# apa102-breakout.net
KiCad netlist of a schematic drawn in EAGLE
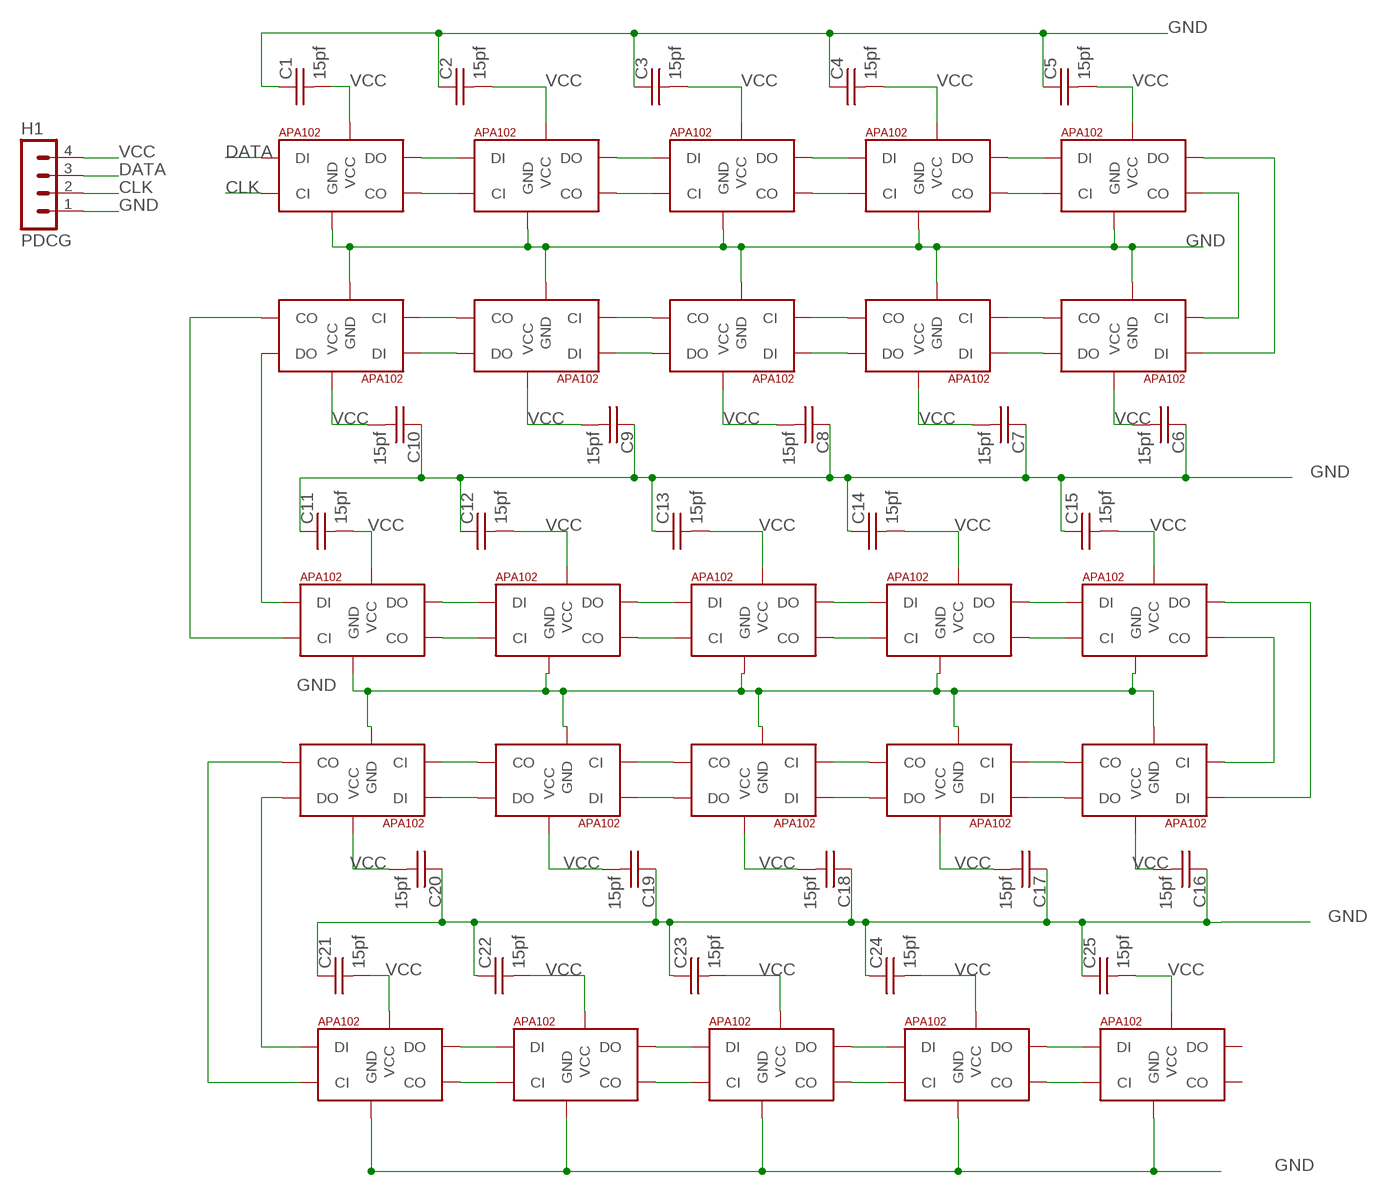
[diagram p0: schematic, sheet 1]
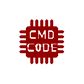
[diagram p1: schematic, sheet 2]

(export (version "E")
  (design (tool "Eeschema 10.0.6"))
  (components
    (comp (ref "C1")
      (value "15pf")
      (footprint "eagle-import:C0805")
      (libsource (lib "eagle-import") (part "C-USC0805"))
    )
    (comp (ref "C2")
      (value "15pf")
      (footprint "eagle-import:C0805")
      (libsource (lib "eagle-import") (part "C-USC0805"))
    )
    (comp (ref "C3")
      (value "15pf")
      (footprint "eagle-import:C0805")
      (libsource (lib "eagle-import") (part "C-USC0805"))
    )
    (comp (ref "C4")
      (value "15pf")
      (footprint "eagle-import:C0805")
      (libsource (lib "eagle-import") (part "C-USC0805"))
    )
    (comp (ref "C5")
      (value "15pf")
      (footprint "eagle-import:C0805")
      (libsource (lib "eagle-import") (part "C-USC0805"))
    )
    (comp (ref "C6")
      (value "15pf")
      (footprint "eagle-import:C0805")
      (libsource (lib "eagle-import") (part "C-USC0805"))
    )
    (comp (ref "C7")
      (value "15pf")
      (footprint "eagle-import:C0805")
      (libsource (lib "eagle-import") (part "C-USC0805"))
    )
    (comp (ref "C8")
      (value "15pf")
      (footprint "eagle-import:C0805")
      (libsource (lib "eagle-import") (part "C-USC0805"))
    )
    (comp (ref "C9")
      (value "15pf")
      (footprint "eagle-import:C0805")
      (libsource (lib "eagle-import") (part "C-USC0805"))
    )
    (comp (ref "C10")
      (value "15pf")
      (footprint "eagle-import:C0805")
      (libsource (lib "eagle-import") (part "C-USC0805"))
    )
    (comp (ref "C11")
      (value "15pf")
      (footprint "eagle-import:C0805")
      (libsource (lib "eagle-import") (part "C-USC0805"))
    )
    (comp (ref "C12")
      (value "15pf")
      (footprint "eagle-import:C0805")
      (libsource (lib "eagle-import") (part "C-USC0805"))
    )
    (comp (ref "C13")
      (value "15pf")
      (footprint "eagle-import:C0805")
      (libsource (lib "eagle-import") (part "C-USC0805"))
    )
    (comp (ref "C14")
      (value "15pf")
      (footprint "eagle-import:C0805")
      (libsource (lib "eagle-import") (part "C-USC0805"))
    )
    (comp (ref "C15")
      (value "15pf")
      (footprint "eagle-import:C0805")
      (libsource (lib "eagle-import") (part "C-USC0805"))
    )
    (comp (ref "C16")
      (value "15pf")
      (footprint "eagle-import:C0805")
      (libsource (lib "eagle-import") (part "C-USC0805"))
    )
    (comp (ref "C17")
      (value "15pf")
      (footprint "eagle-import:C0805")
      (libsource (lib "eagle-import") (part "C-USC0805"))
    )
    (comp (ref "C18")
      (value "15pf")
      (footprint "eagle-import:C0805")
      (libsource (lib "eagle-import") (part "C-USC0805"))
    )
    (comp (ref "C19")
      (value "15pf")
      (footprint "eagle-import:C0805")
      (libsource (lib "eagle-import") (part "C-USC0805"))
    )
    (comp (ref "C20")
      (value "15pf")
      (footprint "eagle-import:C0805")
      (libsource (lib "eagle-import") (part "C-USC0805"))
    )
    (comp (ref "C21")
      (value "15pf")
      (footprint "eagle-import:C0805")
      (libsource (lib "eagle-import") (part "C-USC0805"))
    )
    (comp (ref "C22")
      (value "15pf")
      (footprint "eagle-import:C0805")
      (libsource (lib "eagle-import") (part "C-USC0805"))
    )
    (comp (ref "C23")
      (value "15pf")
      (footprint "eagle-import:C0805")
      (libsource (lib "eagle-import") (part "C-USC0805"))
    )
    (comp (ref "C24")
      (value "15pf")
      (footprint "eagle-import:C0805")
      (libsource (lib "eagle-import") (part "C-USC0805"))
    )
    (comp (ref "C25")
      (value "15pf")
      (footprint "eagle-import:C0805")
      (libsource (lib "eagle-import") (part "C-USC0805"))
    )
    (comp (ref "H1")
      (value "PDCG")
      (footprint "eagle-import:MA04-1")
      (libsource (lib "eagle-import") (part "MA04-1"))
    )
    (comp (ref "U$2")
      (value "APA1025050")
      (footprint "eagle-import:APA102_5050")
      (libsource (lib "eagle-import") (part "APA1025050"))
    )
    (comp (ref "U$3")
      (value "APA1025050")
      (footprint "eagle-import:APA102_5050")
      (libsource (lib "eagle-import") (part "APA1025050"))
    )
    (comp (ref "U$4")
      (value "APA1025050")
      (footprint "eagle-import:APA102_5050")
      (libsource (lib "eagle-import") (part "APA1025050"))
    )
    (comp (ref "U$5")
      (value "APA1025050")
      (footprint "eagle-import:APA102_5050")
      (libsource (lib "eagle-import") (part "APA1025050"))
    )
    (comp (ref "U$6")
      (value "APA1025050")
      (footprint "eagle-import:APA102_5050")
      (libsource (lib "eagle-import") (part "APA1025050"))
    )
    (comp (ref "U$7")
      (value "APA1025050")
      (footprint "eagle-import:APA102_5050")
      (libsource (lib "eagle-import") (part "APA1025050"))
    )
    (comp (ref "U$8")
      (value "APA1025050")
      (footprint "eagle-import:APA102_5050")
      (libsource (lib "eagle-import") (part "APA1025050"))
    )
    (comp (ref "U$9")
      (value "APA1025050")
      (footprint "eagle-import:APA102_5050")
      (libsource (lib "eagle-import") (part "APA1025050"))
    )
    (comp (ref "U$10")
      (value "APA1025050")
      (footprint "eagle-import:APA102_5050")
      (libsource (lib "eagle-import") (part "APA1025050"))
    )
    (comp (ref "U$11")
      (value "APA1025050")
      (footprint "eagle-import:APA102_5050")
      (libsource (lib "eagle-import") (part "APA1025050"))
    )
    (comp (ref "U$12")
      (value "APA1025050")
      (footprint "eagle-import:APA102_5050")
      (libsource (lib "eagle-import") (part "APA1025050"))
    )
    (comp (ref "U$13")
      (value "APA1025050")
      (footprint "eagle-import:APA102_5050")
      (libsource (lib "eagle-import") (part "APA1025050"))
    )
    (comp (ref "U$14")
      (value "APA1025050")
      (footprint "eagle-import:APA102_5050")
      (libsource (lib "eagle-import") (part "APA1025050"))
    )
    (comp (ref "U$15")
      (value "APA1025050")
      (footprint "eagle-import:APA102_5050")
      (libsource (lib "eagle-import") (part "APA1025050"))
    )
    (comp (ref "U$16")
      (value "APA1025050")
      (footprint "eagle-import:APA102_5050")
      (libsource (lib "eagle-import") (part "APA1025050"))
    )
    (comp (ref "U$17")
      (value "APA1025050")
      (footprint "eagle-import:APA102_5050")
      (libsource (lib "eagle-import") (part "APA1025050"))
    )
    (comp (ref "U$18")
      (value "APA1025050")
      (footprint "eagle-import:APA102_5050")
      (libsource (lib "eagle-import") (part "APA1025050"))
    )
    (comp (ref "U$19")
      (value "APA1025050")
      (footprint "eagle-import:APA102_5050")
      (libsource (lib "eagle-import") (part "APA1025050"))
    )
    (comp (ref "U$20")
      (value "APA1025050")
      (footprint "eagle-import:APA102_5050")
      (libsource (lib "eagle-import") (part "APA1025050"))
    )
    (comp (ref "U$21")
      (value "APA1025050")
      (footprint "eagle-import:APA102_5050")
      (libsource (lib "eagle-import") (part "APA1025050"))
    )
    (comp (ref "U$22")
      (value "APA1025050")
      (footprint "eagle-import:APA102_5050")
      (libsource (lib "eagle-import") (part "APA1025050"))
    )
    (comp (ref "U$23")
      (value "APA1025050")
      (footprint "eagle-import:APA102_5050")
      (libsource (lib "eagle-import") (part "APA1025050"))
    )
    (comp (ref "U$24")
      (value "APA1025050")
      (footprint "eagle-import:APA102_5050")
      (libsource (lib "eagle-import") (part "APA1025050"))
    )
    (comp (ref "U$25")
      (value "APA1025050")
      (footprint "eagle-import:APA102_5050")
      (libsource (lib "eagle-import") (part "APA1025050"))
    )
    (comp (ref "U$26")
      (value "APA1025050")
      (footprint "eagle-import:APA102_5050")
      (libsource (lib "eagle-import") (part "APA1025050"))
    )
    (comp (ref "U$1")
      (value "CMD_C0DE_LOGOCMD_C0DE_LOGO_TOP")
      (footprint "eagle-import:CMD_C0DE_LOGO_TOP")
      (libsource (lib "eagle-import") (part "CMD_C0DE_LOGOCMD_C0DE_LOGO_TOP"))
    )
  )
  (nets
    (net (code "1") (name "CLK") (class "Default")
      (node (ref "H1") (pin "2") (pinfunction "2_2") (pintype "passive"))
      (node (ref "U$2") (pin "5") (pinfunction "CI_5") (pintype "bidirectional"))
    )
    (net (code "2") (name "DATA") (class "Default")
      (node (ref "H1") (pin "3") (pinfunction "3_3") (pintype "passive"))
      (node (ref "U$2") (pin "4") (pinfunction "DI_4") (pintype "bidirectional"))
    )
    (net (code "3") (name "GND") (class "Default")
      (node (ref "C1") (pin "1") (pinfunction "1_1") (pintype "passive"))
      (node (ref "C10") (pin "1") (pinfunction "1_1") (pintype "passive"))
      (node (ref "C11") (pin "1") (pinfunction "1_1") (pintype "passive"))
      (node (ref "C12") (pin "1") (pinfunction "1_1") (pintype "passive"))
      (node (ref "C13") (pin "1") (pinfunction "1_1") (pintype "passive"))
      (node (ref "C14") (pin "1") (pinfunction "1_1") (pintype "passive"))
      (node (ref "C15") (pin "1") (pinfunction "1_1") (pintype "passive"))
      (node (ref "C16") (pin "1") (pinfunction "1_1") (pintype "passive"))
      (node (ref "C17") (pin "1") (pinfunction "1_1") (pintype "passive"))
      (node (ref "C18") (pin "1") (pinfunction "1_1") (pintype "passive"))
      (node (ref "C19") (pin "1") (pinfunction "1_1") (pintype "passive"))
      (node (ref "C2") (pin "1") (pinfunction "1_1") (pintype "passive"))
      (node (ref "C20") (pin "1") (pinfunction "1_1") (pintype "passive"))
      (node (ref "C21") (pin "1") (pinfunction "1_1") (pintype "passive"))
      (node (ref "C22") (pin "1") (pinfunction "1_1") (pintype "passive"))
      (node (ref "C23") (pin "1") (pinfunction "1_1") (pintype "passive"))
      (node (ref "C24") (pin "1") (pinfunction "1_1") (pintype "passive"))
      (node (ref "C25") (pin "1") (pinfunction "1_1") (pintype "passive"))
      (node (ref "C3") (pin "1") (pinfunction "1_1") (pintype "passive"))
      (node (ref "C4") (pin "1") (pinfunction "1_1") (pintype "passive"))
      (node (ref "C5") (pin "1") (pinfunction "1_1") (pintype "passive"))
      (node (ref "C6") (pin "1") (pinfunction "1_1") (pintype "passive"))
      (node (ref "C7") (pin "1") (pinfunction "1_1") (pintype "passive"))
      (node (ref "C8") (pin "1") (pinfunction "1_1") (pintype "passive"))
      (node (ref "C9") (pin "1") (pinfunction "1_1") (pintype "passive"))
      (node (ref "H1") (pin "1") (pinfunction "1_1") (pintype "passive"))
      (node (ref "U$10") (pin "6") (pinfunction "GND_6") (pintype "bidirectional"))
      (node (ref "U$11") (pin "6") (pinfunction "GND_6") (pintype "bidirectional"))
      (node (ref "U$12") (pin "6") (pinfunction "GND_6") (pintype "bidirectional"))
      (node (ref "U$13") (pin "6") (pinfunction "GND_6") (pintype "bidirectional"))
      (node (ref "U$14") (pin "6") (pinfunction "GND_6") (pintype "bidirectional"))
      (node (ref "U$15") (pin "6") (pinfunction "GND_6") (pintype "bidirectional"))
      (node (ref "U$16") (pin "6") (pinfunction "GND_6") (pintype "bidirectional"))
      (node (ref "U$17") (pin "6") (pinfunction "GND_6") (pintype "bidirectional"))
      (node (ref "U$18") (pin "6") (pinfunction "GND_6") (pintype "bidirectional"))
      (node (ref "U$19") (pin "6") (pinfunction "GND_6") (pintype "bidirectional"))
      (node (ref "U$2") (pin "6") (pinfunction "GND_6") (pintype "bidirectional"))
      (node (ref "U$20") (pin "6") (pinfunction "GND_6") (pintype "bidirectional"))
      (node (ref "U$21") (pin "6") (pinfunction "GND_6") (pintype "bidirectional"))
      (node (ref "U$22") (pin "6") (pinfunction "GND_6") (pintype "bidirectional"))
      (node (ref "U$23") (pin "6") (pinfunction "GND_6") (pintype "bidirectional"))
      (node (ref "U$24") (pin "6") (pinfunction "GND_6") (pintype "bidirectional"))
      (node (ref "U$25") (pin "6") (pinfunction "GND_6") (pintype "bidirectional"))
      (node (ref "U$26") (pin "6") (pinfunction "GND_6") (pintype "bidirectional"))
      (node (ref "U$3") (pin "6") (pinfunction "GND_6") (pintype "bidirectional"))
      (node (ref "U$4") (pin "6") (pinfunction "GND_6") (pintype "bidirectional"))
      (node (ref "U$5") (pin "6") (pinfunction "GND_6") (pintype "bidirectional"))
      (node (ref "U$6") (pin "6") (pinfunction "GND_6") (pintype "bidirectional"))
      (node (ref "U$7") (pin "6") (pinfunction "GND_6") (pintype "bidirectional"))
      (node (ref "U$8") (pin "6") (pinfunction "GND_6") (pintype "bidirectional"))
      (node (ref "U$9") (pin "6") (pinfunction "GND_6") (pintype "bidirectional"))
    )
    (net (code "4") (name "Net-(U$2-CO)") (class "Default")
      (node (ref "U$2") (pin "2") (pinfunction "CO_2") (pintype "bidirectional"))
      (node (ref "U$3") (pin "5") (pinfunction "CI_5") (pintype "bidirectional"))
    )
    (net (code "5") (name "Net-(U$2-DO)") (class "Default")
      (node (ref "U$2") (pin "3") (pinfunction "DO_3") (pintype "bidirectional"))
      (node (ref "U$3") (pin "4") (pinfunction "DI_4") (pintype "bidirectional"))
    )
    (net (code "6") (name "Net-(U$3-CO)") (class "Default")
      (node (ref "U$3") (pin "2") (pinfunction "CO_2") (pintype "bidirectional"))
      (node (ref "U$4") (pin "5") (pinfunction "CI_5") (pintype "bidirectional"))
    )
    (net (code "7") (name "Net-(U$3-DO)") (class "Default")
      (node (ref "U$3") (pin "3") (pinfunction "DO_3") (pintype "bidirectional"))
      (node (ref "U$4") (pin "4") (pinfunction "DI_4") (pintype "bidirectional"))
    )
    (net (code "8") (name "Net-(U$4-CO)") (class "Default")
      (node (ref "U$4") (pin "2") (pinfunction "CO_2") (pintype "bidirectional"))
      (node (ref "U$5") (pin "5") (pinfunction "CI_5") (pintype "bidirectional"))
    )
    (net (code "9") (name "Net-(U$4-DO)") (class "Default")
      (node (ref "U$4") (pin "3") (pinfunction "DO_3") (pintype "bidirectional"))
      (node (ref "U$5") (pin "4") (pinfunction "DI_4") (pintype "bidirectional"))
    )
    (net (code "10") (name "Net-(U$5-CO)") (class "Default")
      (node (ref "U$5") (pin "2") (pinfunction "CO_2") (pintype "bidirectional"))
      (node (ref "U$6") (pin "5") (pinfunction "CI_5") (pintype "bidirectional"))
    )
    (net (code "11") (name "Net-(U$5-DO)") (class "Default")
      (node (ref "U$5") (pin "3") (pinfunction "DO_3") (pintype "bidirectional"))
      (node (ref "U$6") (pin "4") (pinfunction "DI_4") (pintype "bidirectional"))
    )
    (net (code "12") (name "Net-(U$6-CO)") (class "Default")
      (node (ref "U$6") (pin "2") (pinfunction "CO_2") (pintype "bidirectional"))
      (node (ref "U$7") (pin "5") (pinfunction "CI_5") (pintype "bidirectional"))
    )
    (net (code "13") (name "Net-(U$6-DO)") (class "Default")
      (node (ref "U$6") (pin "3") (pinfunction "DO_3") (pintype "bidirectional"))
      (node (ref "U$7") (pin "4") (pinfunction "DI_4") (pintype "bidirectional"))
    )
    (net (code "14") (name "Net-(U$7-CO)") (class "Default")
      (node (ref "U$7") (pin "2") (pinfunction "CO_2") (pintype "bidirectional"))
      (node (ref "U$8") (pin "5") (pinfunction "CI_5") (pintype "bidirectional"))
    )
    (net (code "15") (name "Net-(U$7-DO)") (class "Default")
      (node (ref "U$7") (pin "3") (pinfunction "DO_3") (pintype "bidirectional"))
      (node (ref "U$8") (pin "4") (pinfunction "DI_4") (pintype "bidirectional"))
    )
    (net (code "16") (name "Net-(U$8-CO)") (class "Default")
      (node (ref "U$8") (pin "2") (pinfunction "CO_2") (pintype "bidirectional"))
      (node (ref "U$9") (pin "5") (pinfunction "CI_5") (pintype "bidirectional"))
    )
    (net (code "17") (name "Net-(U$8-DO)") (class "Default")
      (node (ref "U$8") (pin "3") (pinfunction "DO_3") (pintype "bidirectional"))
      (node (ref "U$9") (pin "4") (pinfunction "DI_4") (pintype "bidirectional"))
    )
    (net (code "18") (name "Net-(U$10-CI)") (class "Default")
      (node (ref "U$10") (pin "5") (pinfunction "CI_5") (pintype "bidirectional"))
      (node (ref "U$9") (pin "2") (pinfunction "CO_2") (pintype "bidirectional"))
    )
    (net (code "19") (name "Net-(U$10-CO)") (class "Default")
      (node (ref "U$10") (pin "2") (pinfunction "CO_2") (pintype "bidirectional"))
      (node (ref "U$11") (pin "5") (pinfunction "CI_5") (pintype "bidirectional"))
    )
    (net (code "20") (name "Net-(U$10-DI)") (class "Default")
      (node (ref "U$10") (pin "4") (pinfunction "DI_4") (pintype "bidirectional"))
      (node (ref "U$9") (pin "3") (pinfunction "DO_3") (pintype "bidirectional"))
    )
    (net (code "21") (name "Net-(U$10-DO)") (class "Default")
      (node (ref "U$10") (pin "3") (pinfunction "DO_3") (pintype "bidirectional"))
      (node (ref "U$11") (pin "4") (pinfunction "DI_4") (pintype "bidirectional"))
    )
    (net (code "22") (name "Net-(U$11-CO)") (class "Default")
      (node (ref "U$11") (pin "2") (pinfunction "CO_2") (pintype "bidirectional"))
      (node (ref "U$12") (pin "5") (pinfunction "CI_5") (pintype "bidirectional"))
    )
    (net (code "23") (name "Net-(U$11-DO)") (class "Default")
      (node (ref "U$11") (pin "3") (pinfunction "DO_3") (pintype "bidirectional"))
      (node (ref "U$12") (pin "4") (pinfunction "DI_4") (pintype "bidirectional"))
    )
    (net (code "24") (name "Net-(U$12-CO)") (class "Default")
      (node (ref "U$12") (pin "2") (pinfunction "CO_2") (pintype "bidirectional"))
      (node (ref "U$13") (pin "5") (pinfunction "CI_5") (pintype "bidirectional"))
    )
    (net (code "25") (name "Net-(U$12-DO)") (class "Default")
      (node (ref "U$12") (pin "3") (pinfunction "DO_3") (pintype "bidirectional"))
      (node (ref "U$13") (pin "4") (pinfunction "DI_4") (pintype "bidirectional"))
    )
    (net (code "26") (name "Net-(U$13-CO)") (class "Default")
      (node (ref "U$13") (pin "2") (pinfunction "CO_2") (pintype "bidirectional"))
      (node (ref "U$14") (pin "5") (pinfunction "CI_5") (pintype "bidirectional"))
    )
    (net (code "27") (name "Net-(U$13-DO)") (class "Default")
      (node (ref "U$13") (pin "3") (pinfunction "DO_3") (pintype "bidirectional"))
      (node (ref "U$14") (pin "4") (pinfunction "DI_4") (pintype "bidirectional"))
    )
    (net (code "28") (name "Net-(U$14-CO)") (class "Default")
      (node (ref "U$14") (pin "2") (pinfunction "CO_2") (pintype "bidirectional"))
      (node (ref "U$15") (pin "5") (pinfunction "CI_5") (pintype "bidirectional"))
    )
    (net (code "29") (name "Net-(U$14-DO)") (class "Default")
      (node (ref "U$14") (pin "3") (pinfunction "DO_3") (pintype "bidirectional"))
      (node (ref "U$15") (pin "4") (pinfunction "DI_4") (pintype "bidirectional"))
    )
    (net (code "30") (name "Net-(U$15-CO)") (class "Default")
      (node (ref "U$15") (pin "2") (pinfunction "CO_2") (pintype "bidirectional"))
      (node (ref "U$16") (pin "5") (pinfunction "CI_5") (pintype "bidirectional"))
    )
    (net (code "31") (name "Net-(U$15-DO)") (class "Default")
      (node (ref "U$15") (pin "3") (pinfunction "DO_3") (pintype "bidirectional"))
      (node (ref "U$16") (pin "4") (pinfunction "DI_4") (pintype "bidirectional"))
    )
    (net (code "32") (name "Net-(U$16-CO)") (class "Default")
      (node (ref "U$16") (pin "2") (pinfunction "CO_2") (pintype "bidirectional"))
      (node (ref "U$17") (pin "5") (pinfunction "CI_5") (pintype "bidirectional"))
    )
    (net (code "33") (name "Net-(U$16-DO)") (class "Default")
      (node (ref "U$16") (pin "3") (pinfunction "DO_3") (pintype "bidirectional"))
      (node (ref "U$17") (pin "4") (pinfunction "DI_4") (pintype "bidirectional"))
    )
    (net (code "34") (name "Net-(U$17-CO)") (class "Default")
      (node (ref "U$17") (pin "2") (pinfunction "CO_2") (pintype "bidirectional"))
      (node (ref "U$18") (pin "5") (pinfunction "CI_5") (pintype "bidirectional"))
    )
    (net (code "35") (name "Net-(U$17-DO)") (class "Default")
      (node (ref "U$17") (pin "3") (pinfunction "DO_3") (pintype "bidirectional"))
      (node (ref "U$18") (pin "4") (pinfunction "DI_4") (pintype "bidirectional"))
    )
    (net (code "36") (name "Net-(U$18-CO)") (class "Default")
      (node (ref "U$18") (pin "2") (pinfunction "CO_2") (pintype "bidirectional"))
      (node (ref "U$19") (pin "5") (pinfunction "CI_5") (pintype "bidirectional"))
    )
    (net (code "37") (name "Net-(U$18-DO)") (class "Default")
      (node (ref "U$18") (pin "3") (pinfunction "DO_3") (pintype "bidirectional"))
      (node (ref "U$19") (pin "4") (pinfunction "DI_4") (pintype "bidirectional"))
    )
    (net (code "38") (name "Net-(U$19-CO)") (class "Default")
      (node (ref "U$19") (pin "2") (pinfunction "CO_2") (pintype "bidirectional"))
      (node (ref "U$20") (pin "5") (pinfunction "CI_5") (pintype "bidirectional"))
    )
    (net (code "39") (name "Net-(U$19-DO)") (class "Default")
      (node (ref "U$19") (pin "3") (pinfunction "DO_3") (pintype "bidirectional"))
      (node (ref "U$20") (pin "4") (pinfunction "DI_4") (pintype "bidirectional"))
    )
    (net (code "40") (name "Net-(U$20-CO)") (class "Default")
      (node (ref "U$20") (pin "2") (pinfunction "CO_2") (pintype "bidirectional"))
      (node (ref "U$21") (pin "5") (pinfunction "CI_5") (pintype "bidirectional"))
    )
    (net (code "41") (name "Net-(U$20-DO)") (class "Default")
      (node (ref "U$20") (pin "3") (pinfunction "DO_3") (pintype "bidirectional"))
      (node (ref "U$21") (pin "4") (pinfunction "DI_4") (pintype "bidirectional"))
    )
    (net (code "42") (name "Net-(U$21-CO)") (class "Default")
      (node (ref "U$21") (pin "2") (pinfunction "CO_2") (pintype "bidirectional"))
      (node (ref "U$22") (pin "5") (pinfunction "CI_5") (pintype "bidirectional"))
    )
    (net (code "43") (name "Net-(U$21-DO)") (class "Default")
      (node (ref "U$21") (pin "3") (pinfunction "DO_3") (pintype "bidirectional"))
      (node (ref "U$22") (pin "4") (pinfunction "DI_4") (pintype "bidirectional"))
    )
    (net (code "44") (name "Net-(U$22-CO)") (class "Default")
      (node (ref "U$22") (pin "2") (pinfunction "CO_2") (pintype "bidirectional"))
      (node (ref "U$23") (pin "5") (pinfunction "CI_5") (pintype "bidirectional"))
    )
    (net (code "45") (name "Net-(U$22-DO)") (class "Default")
      (node (ref "U$22") (pin "3") (pinfunction "DO_3") (pintype "bidirectional"))
      (node (ref "U$23") (pin "4") (pinfunction "DI_4") (pintype "bidirectional"))
    )
    (net (code "46") (name "Net-(U$23-CO)") (class "Default")
      (node (ref "U$23") (pin "2") (pinfunction "CO_2") (pintype "bidirectional"))
      (node (ref "U$24") (pin "5") (pinfunction "CI_5") (pintype "bidirectional"))
    )
    (net (code "47") (name "Net-(U$23-DO)") (class "Default")
      (node (ref "U$23") (pin "3") (pinfunction "DO_3") (pintype "bidirectional"))
      (node (ref "U$24") (pin "4") (pinfunction "DI_4") (pintype "bidirectional"))
    )
    (net (code "48") (name "Net-(U$24-CO)") (class "Default")
      (node (ref "U$24") (pin "2") (pinfunction "CO_2") (pintype "bidirectional"))
      (node (ref "U$25") (pin "5") (pinfunction "CI_5") (pintype "bidirectional"))
    )
    (net (code "49") (name "Net-(U$24-DO)") (class "Default")
      (node (ref "U$24") (pin "3") (pinfunction "DO_3") (pintype "bidirectional"))
      (node (ref "U$25") (pin "4") (pinfunction "DI_4") (pintype "bidirectional"))
    )
    (net (code "50") (name "Net-(U$25-CO)") (class "Default")
      (node (ref "U$25") (pin "2") (pinfunction "CO_2") (pintype "bidirectional"))
      (node (ref "U$26") (pin "5") (pinfunction "CI_5") (pintype "bidirectional"))
    )
    (net (code "51") (name "Net-(U$25-DO)") (class "Default")
      (node (ref "U$25") (pin "3") (pinfunction "DO_3") (pintype "bidirectional"))
      (node (ref "U$26") (pin "4") (pinfunction "DI_4") (pintype "bidirectional"))
    )
    (net (code "52") (name "VCC") (class "Default")
      (node (ref "C1") (pin "2") (pinfunction "2_2") (pintype "passive"))
      (node (ref "C10") (pin "2") (pinfunction "2_2") (pintype "passive"))
      (node (ref "C11") (pin "2") (pinfunction "2_2") (pintype "passive"))
      (node (ref "C12") (pin "2") (pinfunction "2_2") (pintype "passive"))
      (node (ref "C13") (pin "2") (pinfunction "2_2") (pintype "passive"))
      (node (ref "C14") (pin "2") (pinfunction "2_2") (pintype "passive"))
      (node (ref "C15") (pin "2") (pinfunction "2_2") (pintype "passive"))
      (node (ref "C16") (pin "2") (pinfunction "2_2") (pintype "passive"))
      (node (ref "C17") (pin "2") (pinfunction "2_2") (pintype "passive"))
      (node (ref "C18") (pin "2") (pinfunction "2_2") (pintype "passive"))
      (node (ref "C19") (pin "2") (pinfunction "2_2") (pintype "passive"))
      (node (ref "C2") (pin "2") (pinfunction "2_2") (pintype "passive"))
      (node (ref "C20") (pin "2") (pinfunction "2_2") (pintype "passive"))
      (node (ref "C21") (pin "2") (pinfunction "2_2") (pintype "passive"))
      (node (ref "C22") (pin "2") (pinfunction "2_2") (pintype "passive"))
      (node (ref "C23") (pin "2") (pinfunction "2_2") (pintype "passive"))
      (node (ref "C24") (pin "2") (pinfunction "2_2") (pintype "passive"))
      (node (ref "C25") (pin "2") (pinfunction "2_2") (pintype "passive"))
      (node (ref "C3") (pin "2") (pinfunction "2_2") (pintype "passive"))
      (node (ref "C4") (pin "2") (pinfunction "2_2") (pintype "passive"))
      (node (ref "C5") (pin "2") (pinfunction "2_2") (pintype "passive"))
      (node (ref "C6") (pin "2") (pinfunction "2_2") (pintype "passive"))
      (node (ref "C7") (pin "2") (pinfunction "2_2") (pintype "passive"))
      (node (ref "C8") (pin "2") (pinfunction "2_2") (pintype "passive"))
      (node (ref "C9") (pin "2") (pinfunction "2_2") (pintype "passive"))
      (node (ref "H1") (pin "4") (pinfunction "4_4") (pintype "passive"))
      (node (ref "U$10") (pin "1") (pinfunction "VCC_1") (pintype "bidirectional"))
      (node (ref "U$11") (pin "1") (pinfunction "VCC_1") (pintype "bidirectional"))
      (node (ref "U$12") (pin "1") (pinfunction "VCC_1") (pintype "bidirectional"))
      (node (ref "U$13") (pin "1") (pinfunction "VCC_1") (pintype "bidirectional"))
      (node (ref "U$14") (pin "1") (pinfunction "VCC_1") (pintype "bidirectional"))
      (node (ref "U$15") (pin "1") (pinfunction "VCC_1") (pintype "bidirectional"))
      (node (ref "U$16") (pin "1") (pinfunction "VCC_1") (pintype "bidirectional"))
      (node (ref "U$17") (pin "1") (pinfunction "VCC_1") (pintype "bidirectional"))
      (node (ref "U$18") (pin "1") (pinfunction "VCC_1") (pintype "bidirectional"))
      (node (ref "U$19") (pin "1") (pinfunction "VCC_1") (pintype "bidirectional"))
      (node (ref "U$2") (pin "1") (pinfunction "VCC_1") (pintype "bidirectional"))
      (node (ref "U$20") (pin "1") (pinfunction "VCC_1") (pintype "bidirectional"))
      (node (ref "U$21") (pin "1") (pinfunction "VCC_1") (pintype "bidirectional"))
      (node (ref "U$22") (pin "1") (pinfunction "VCC_1") (pintype "bidirectional"))
      (node (ref "U$23") (pin "1") (pinfunction "VCC_1") (pintype "bidirectional"))
      (node (ref "U$24") (pin "1") (pinfunction "VCC_1") (pintype "bidirectional"))
      (node (ref "U$25") (pin "1") (pinfunction "VCC_1") (pintype "bidirectional"))
      (node (ref "U$26") (pin "1") (pinfunction "VCC_1") (pintype "bidirectional"))
      (node (ref "U$3") (pin "1") (pinfunction "VCC_1") (pintype "bidirectional"))
      (node (ref "U$4") (pin "1") (pinfunction "VCC_1") (pintype "bidirectional"))
      (node (ref "U$5") (pin "1") (pinfunction "VCC_1") (pintype "bidirectional"))
      (node (ref "U$6") (pin "1") (pinfunction "VCC_1") (pintype "bidirectional"))
      (node (ref "U$7") (pin "1") (pinfunction "VCC_1") (pintype "bidirectional"))
      (node (ref "U$8") (pin "1") (pinfunction "VCC_1") (pintype "bidirectional"))
      (node (ref "U$9") (pin "1") (pinfunction "VCC_1") (pintype "bidirectional"))
    )
    (net (code "53") (name "unconnected-(U$26-CO-Pad2)") (class "Default")
      (node (ref "U$26") (pin "2") (pinfunction "CO_2") (pintype "bidirectional"))
    )
    (net (code "54") (name "unconnected-(U$26-DO-Pad3)") (class "Default")
      (node (ref "U$26") (pin "3") (pinfunction "DO_3") (pintype "bidirectional"))
    )
  )
)
